# Power.net
KiCad netlist of a schematic drawn in Altium Designer
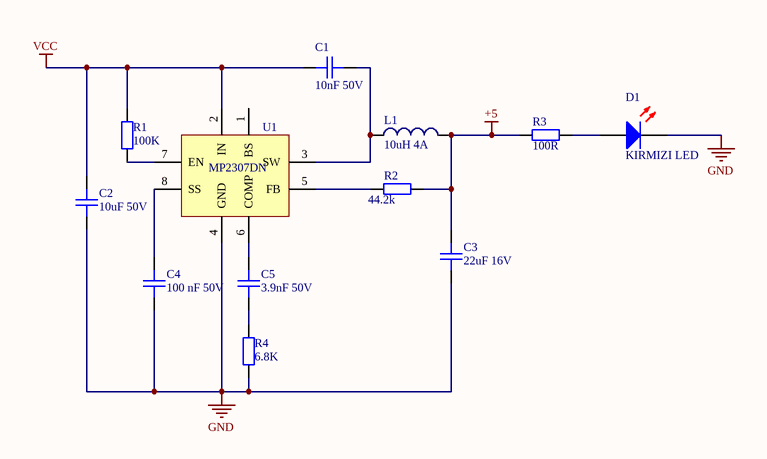
[diagram p0: Power.SchDoc]

(export (version "E")
  (design (tool "Eeschema 10.0.6"))
  (components
    (comp (ref "C1")
      (value "CAP CER 10000PF 50V X7R 0805")
      (footprint "CAP-0805(2012)")
      (description "10000pF ±10% 50V Ceramic Capacitor X7R 0805 (2012 Metric)")
      (fields (field (name "DEGER") "10nF 50V"))
      (libsource (lib "ESC") (part "10nF 50V 0805"))
    )
    (comp (ref "C2")
      (value "CAP CER 10UF 50V X5R 1206")
      (footprint "CAP 1206/3216")
      (description "10µF ±10% 50V Ceramic Capacitor X5R 1206 (3216 Metric)")
      (fields (field (name "DEGER") "10uF 50V"))
      (libsource (lib "ESC") (part "10uF 50V 1206"))
    )
    (comp (ref "C3")
      (value "CAP CERAMIC 22UF 16V X7S 20% PAD")
      (footprint "CAP 1206/3216")
      (description "22µF ±20% 16V Ceramic Capacitor X7S 1206 (3216 Metric)")
      (fields (field (name "DEGER") "22uF 16V"))
      (libsource (lib "ESC") (part "22uF 16V 1206"))
    )
    (comp (ref "C4")
      (value "CAP CER 0.1UF 50V X7R 0805")
      (footprint "CAP-0805(2012)")
      (description "0.1 µF ±10% 50V Ceramic Capacitor X7R 0805 (2012 Metric)")
      (fields (field (name "DEGER") "100 nF 50V"))
      (libsource (lib "ESC") (part "100nF 50V 0805"))
    )
    (comp (ref "C5")
      (value "CAP CER 3900PF 50V X7R 0805")
      (footprint "CAP-0805(2012)")
      (description "3900pF ±10% 50V Ceramic Capacitor X7R 0805 (2012 Metric)")
      (fields (field (name "DEGER") "3.9nF 50V"))
      (libsource (lib "ESC") (part "3.9nF 50V 0805"))
    )
    (comp (ref "D1")
      (value "Red 645nm LED Indication - Discrete 1.8V 0805")
      (footprint "SMD: LED 0805/2012 RED")
      (description "LED RED DIFFUSED 0805 SMD")
      (fields (field (name "DEGER") "KIRMIZI LED"))
      (libsource (lib "ESC") (part "LED_Kırmızı"))
    )
    (comp (ref "L1")
      (value "FIXED IND 10UH 4A 68 MOHM SMD")
      (footprint "ASPI-0630LR-100M-T15")
      (description "10µH Shielded Molded Inductor 4A 68mOhm Max Nonstandard")
      (fields (field (name "DEGER") "10uH 4A"))
      (libsource (lib "ESC") (part "10uH 4A"))
    )
    (comp (ref "R1")
      (value "RES SMD 100K OHM 1% 1/8W 0805")
      (footprint "RES-0805")
      (description "100 kOhms ±1% 0.125W, 1/8W Chip Resistor 0805 (2012 Metric) Moisture Resistant Thick Film")
      (fields (field (name "DEGER") "100K"))
      (libsource (lib "ESC") (part "100K 0805"))
    )
    (comp (ref "R2")
      (value "RES SMD 44.2K OHM 1% 1/8W 0805")
      (footprint "RES-0805")
      (description "44.2 kOhms ±1% 0.125W, 1/8W Chip Resistor 0805 (2012 Metric) Moisture Resistant Thick Film")
      (fields (field (name "DEGER") "44.2k"))
      (libsource (lib "ESC") (part "44.2K 0805"))
    )
    (comp (ref "R3")
      (value "RES SMD 100 OHM 1% 1/8W 0805")
      (footprint "RES-0805")
      (description "100 Ohms ±1% 0.125W, 1/8W Chip Resistor 0805 (2012 Metric) Moisture Resistant Thick Film")
      (fields (field (name "DEGER") "100R"))
      (libsource (lib "ESC") (part "100R 0805"))
    )
    (comp (ref "R4")
      (value "RES SMD 6.8K OHM 1% 1/8W 0805")
      (footprint "RES-0805")
      (description "6.8 kOhms ±1% 0.125W, 1/8W Chip Resistor 0805 (2012 Metric) Moisture Resistant Thick Film")
      (fields (field (name "DEGER") "6.8K"))
      (libsource (lib "ESC") (part "6.8K 0805"))
    )
    (comp (ref "U1")
      (value "IC REG BUCK ADJ 3A 8SOIC")
      (footprint "SOIC8-PAD")
      (fields (field (name "DEGER") "MP2307DN"))
      (libsource (lib "ESC") (part "MP2307DN"))
    )
  )
  (nets
    (net (code "1") (name "+5") (class "Default")
      (node (ref "C3") (pin "2") (pinfunction "2_2") (pintype "passive"))
      (node (ref "L1") (pin "2") (pinfunction "2_2") (pintype "passive"))
      (node (ref "R2") (pin "2") (pinfunction "2_2") (pintype "passive"))
      (node (ref "R3") (pin "1") (pinfunction "1_1") (pintype "passive"))
    )
    (net (code "2") (name "GND") (class "Default")
      (node (ref "C2") (pin "1") (pinfunction "1_1") (pintype "passive"))
      (node (ref "C3") (pin "1") (pinfunction "1_1") (pintype "passive"))
      (node (ref "C4") (pin "1") (pinfunction "1_1") (pintype "passive"))
      (node (ref "D1") (pin "2") (pinfunction "K_2") (pintype "passive"))
      (node (ref "R4") (pin "1") (pinfunction "1_1") (pintype "passive"))
      (node (ref "U1") (pin "4") (pinfunction "GND_4") (pintype "passive"))
    )
    (net (code "3") (name "Net-(C5-Pad1)") (class "Default")
      (node (ref "C5") (pin "1") (pinfunction "1_1") (pintype "passive"))
      (node (ref "R4") (pin "2") (pinfunction "2_2") (pintype "passive"))
    )
    (net (code "4") (name "Net-(D1-A)") (class "Default")
      (node (ref "D1") (pin "1") (pinfunction "A_1") (pintype "passive"))
      (node (ref "R3") (pin "2") (pinfunction "2_2") (pintype "passive"))
    )
    (net (code "5") (name "Net-(U1-COMP)") (class "Default")
      (node (ref "C5") (pin "2") (pinfunction "2_2") (pintype "passive"))
      (node (ref "U1") (pin "6") (pinfunction "COMP_6") (pintype "passive"))
    )
    (net (code "6") (name "Net-(U1-EN)") (class "Default")
      (node (ref "R1") (pin "1") (pinfunction "1_1") (pintype "passive"))
      (node (ref "U1") (pin "7") (pinfunction "EN_7") (pintype "passive"))
    )
    (net (code "7") (name "Net-(U1-FB)") (class "Default")
      (node (ref "R2") (pin "1") (pinfunction "1_1") (pintype "passive"))
      (node (ref "U1") (pin "5") (pinfunction "FB_5") (pintype "passive"))
    )
    (net (code "8") (name "Net-(U1-SS)") (class "Default")
      (node (ref "C4") (pin "2") (pinfunction "2_2") (pintype "passive"))
      (node (ref "U1") (pin "8") (pinfunction "SS_8") (pintype "passive"))
    )
    (net (code "9") (name "Net-(U1-SW)") (class "Default")
      (node (ref "C1") (pin "2") (pinfunction "2_2") (pintype "passive"))
      (node (ref "L1") (pin "1") (pinfunction "1_1") (pintype "passive"))
      (node (ref "U1") (pin "3") (pinfunction "SW_3") (pintype "passive"))
    )
    (net (code "10") (name "VCC") (class "Default")
      (node (ref "C1") (pin "1") (pinfunction "1_1") (pintype "passive"))
      (node (ref "C2") (pin "2") (pinfunction "2_2") (pintype "passive"))
      (node (ref "R1") (pin "2") (pinfunction "2_2") (pintype "passive"))
      (node (ref "U1") (pin "2") (pinfunction "IN_2") (pintype "passive"))
    )
    (net (code "11") (name "unconnected-(U1-BS-Pad1)") (class "Default")
      (node (ref "U1") (pin "1") (pinfunction "BS_1") (pintype "passive"))
    )
  )
)
